# USB_Host.net
KiCad netlist of a schematic drawn in EAGLE
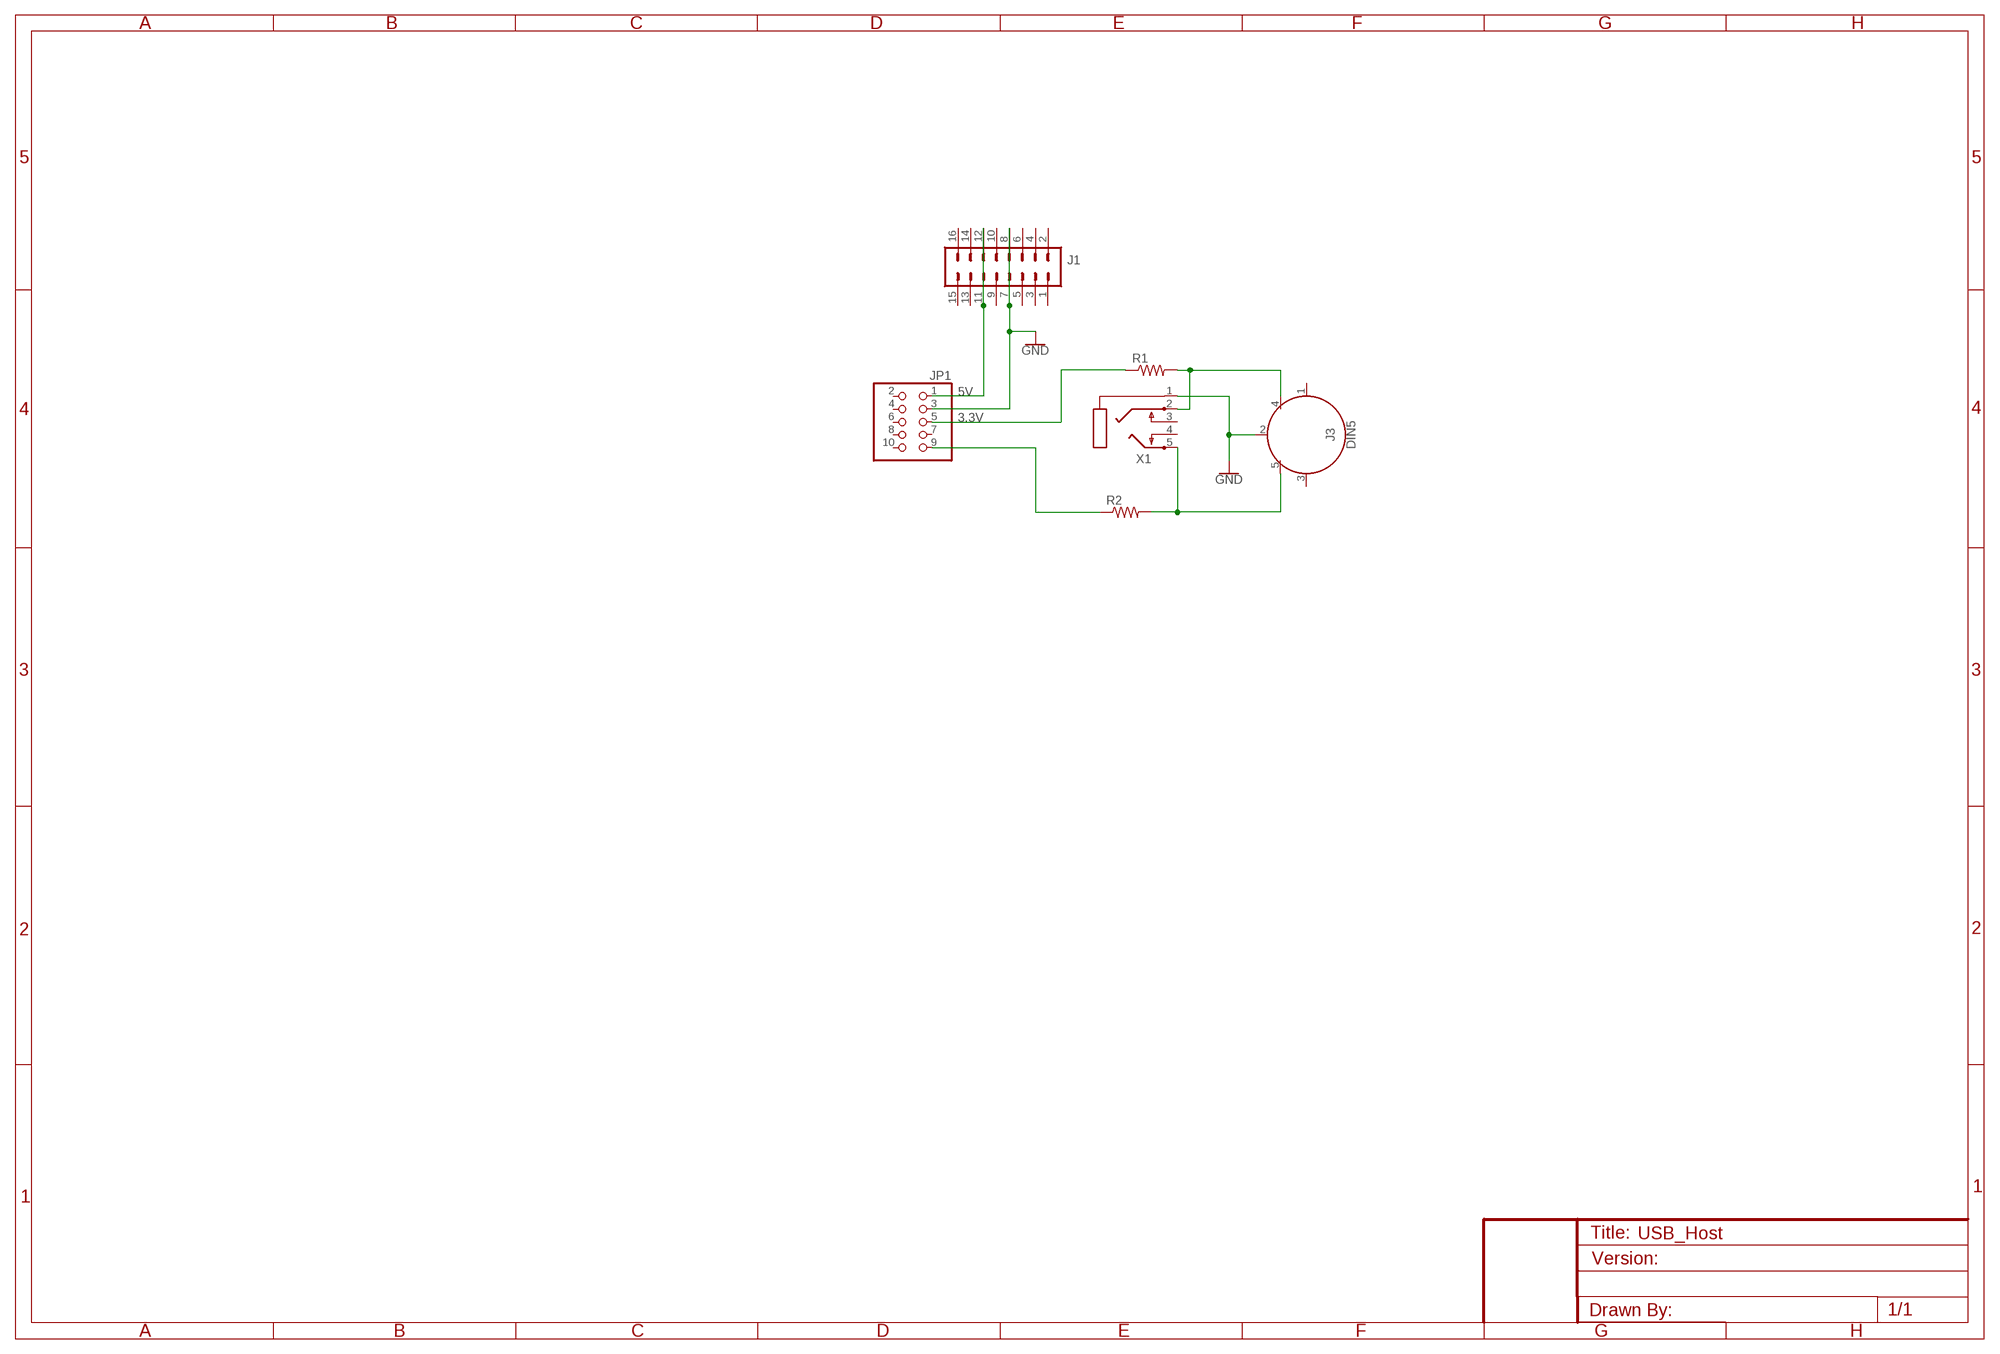
[diagram p0: schematic, sheet 1]

(export (version "E")
  (design (tool "Eeschema 10.0.6"))
  (components
    (comp (ref "J1")
      (value "CONN_08X2_SHROUD")
      (footprint "eagle-import:2X8-SHROUDED_LOCK")
      (libsource (lib "eagle-import") (part "CONN_08X2_SHROUD"))
    )
    (comp (ref "J3")
      (value "DIN5")
      (footprint "eagle-import:DIN5-RA-PTH")
      (libsource (lib "eagle-import") (part "DIN5"))
    )
    (comp (ref "JP1")
      (value "PINHD-2X5")
      (footprint "eagle-import:2X05")
      (libsource (lib "eagle-import") (part "PINHD-2X5"))
    )
    (comp (ref "R1")
      (value "68")
      (footprint "eagle-import:0204_7")
      (libsource (lib "eagle-import") (part "R-US_0204/7"))
    )
    (comp (ref "R2")
      (value "68")
      (footprint "eagle-import:0204_7")
      (libsource (lib "eagle-import") (part "R-US_0204/7"))
    )
    (comp (ref "X1")
      (value "PG203J")
      (footprint "eagle-import:PG203J")
      (libsource (lib "eagle-import") (part "PG203J"))
    )
  )
  (nets
    (net (code "1") (name "/3.3V") (class "Default")
      (node (ref "JP1") (pin "5") (pinfunction "5_5") (pintype "passive"))
      (node (ref "R1") (pin "1") (pinfunction "1_1") (pintype "passive"))
    )
    (net (code "2") (name "/5V") (class "Default")
      (node (ref "J1") (pin "11") (pinfunction "11_11") (pintype "passive"))
      (node (ref "J1") (pin "12") (pinfunction "12_12") (pintype "passive"))
      (node (ref "JP1") (pin "1") (pinfunction "1_1") (pintype "passive"))
    )
    (net (code "3") (name "GND") (class "Default")
      (node (ref "J1") (pin "7") (pinfunction "7_7") (pintype "passive"))
      (node (ref "J1") (pin "8") (pinfunction "8_8") (pintype "passive"))
      (node (ref "J3") (pin "2") (pinfunction "2_2") (pintype "bidirectional"))
      (node (ref "JP1") (pin "3") (pinfunction "3_3") (pintype "passive"))
      (node (ref "X1") (pin "1") (pinfunction "1_1") (pintype "passive"))
    )
    (net (code "4") (name "Net-(J3-Pad4)") (class "Default")
      (node (ref "J3") (pin "4") (pinfunction "4_4") (pintype "bidirectional"))
      (node (ref "R1") (pin "2") (pinfunction "2_2") (pintype "passive"))
      (node (ref "X1") (pin "2") (pinfunction "2_2") (pintype "passive"))
    )
    (net (code "5") (name "Net-(J3-Pad5)") (class "Default")
      (node (ref "J3") (pin "5") (pinfunction "5_5") (pintype "bidirectional"))
      (node (ref "R2") (pin "2") (pinfunction "2_2") (pintype "passive"))
      (node (ref "X1") (pin "5") (pinfunction "5_5") (pintype "passive"))
    )
    (net (code "6") (name "Net-(JP1-Pad9)") (class "Default")
      (node (ref "JP1") (pin "9") (pinfunction "9_9") (pintype "passive"))
      (node (ref "R2") (pin "1") (pinfunction "1_1") (pintype "passive"))
    )
    (net (code "7") (name "unconnected-(J1-Pad1)") (class "Default")
      (node (ref "J1") (pin "1") (pinfunction "1_1") (pintype "passive"))
    )
    (net (code "8") (name "unconnected-(J1-Pad2)") (class "Default")
      (node (ref "J1") (pin "2") (pinfunction "2_2") (pintype "passive"))
    )
    (net (code "9") (name "unconnected-(J1-Pad3)") (class "Default")
      (node (ref "J1") (pin "3") (pinfunction "3_3") (pintype "passive"))
    )
    (net (code "10") (name "unconnected-(J1-Pad4)") (class "Default")
      (node (ref "J1") (pin "4") (pinfunction "4_4") (pintype "passive"))
    )
    (net (code "11") (name "unconnected-(J1-Pad5)") (class "Default")
      (node (ref "J1") (pin "5") (pinfunction "5_5") (pintype "passive"))
    )
    (net (code "12") (name "unconnected-(J1-Pad6)") (class "Default")
      (node (ref "J1") (pin "6") (pinfunction "6_6") (pintype "passive"))
    )
    (net (code "13") (name "unconnected-(J1-Pad9)") (class "Default")
      (node (ref "J1") (pin "9") (pinfunction "9_9") (pintype "passive"))
    )
    (net (code "14") (name "unconnected-(J1-Pad10)") (class "Default")
      (node (ref "J1") (pin "10") (pinfunction "10_10") (pintype "passive"))
    )
    (net (code "15") (name "unconnected-(J1-Pad13)") (class "Default")
      (node (ref "J1") (pin "13") (pinfunction "13_13") (pintype "passive"))
    )
    (net (code "16") (name "unconnected-(J1-Pad14)") (class "Default")
      (node (ref "J1") (pin "14") (pinfunction "14_14") (pintype "passive"))
    )
    (net (code "17") (name "unconnected-(J1-Pad15)") (class "Default")
      (node (ref "J1") (pin "15") (pinfunction "15_15") (pintype "passive"))
    )
    (net (code "18") (name "unconnected-(J1-Pad16)") (class "Default")
      (node (ref "J1") (pin "16") (pinfunction "16_16") (pintype "passive"))
    )
    (net (code "19") (name "unconnected-(J3-Pad1)") (class "Default")
      (node (ref "J3") (pin "1") (pinfunction "1_1") (pintype "bidirectional"))
    )
    (net (code "20") (name "unconnected-(J3-Pad3)") (class "Default")
      (node (ref "J3") (pin "3") (pinfunction "3_3") (pintype "bidirectional"))
    )
    (net (code "21") (name "unconnected-(JP1-Pad2)") (class "Default")
      (node (ref "JP1") (pin "2") (pinfunction "2_2") (pintype "passive"))
    )
    (net (code "22") (name "unconnected-(JP1-Pad4)") (class "Default")
      (node (ref "JP1") (pin "4") (pinfunction "4_4") (pintype "passive"))
    )
    (net (code "23") (name "unconnected-(JP1-Pad6)") (class "Default")
      (node (ref "JP1") (pin "6") (pinfunction "6_6") (pintype "passive"))
    )
    (net (code "24") (name "unconnected-(JP1-Pad7)") (class "Default")
      (node (ref "JP1") (pin "7") (pinfunction "7_7") (pintype "passive"))
    )
    (net (code "25") (name "unconnected-(JP1-Pad8)") (class "Default")
      (node (ref "JP1") (pin "8") (pinfunction "8_8") (pintype "passive"))
    )
    (net (code "26") (name "unconnected-(JP1-Pad10)") (class "Default")
      (node (ref "JP1") (pin "10") (pinfunction "10_10") (pintype "passive"))
    )
    (net (code "27") (name "unconnected-(X1-Pad3)") (class "Default")
      (node (ref "X1") (pin "3") (pinfunction "3_3") (pintype "passive"))
    )
    (net (code "28") (name "unconnected-(X1-Pad4)") (class "Default")
      (node (ref "X1") (pin "4") (pinfunction "4_4") (pintype "passive"))
    )
  )
)
